# connectors.net
KiCad netlist of a schematic drawn in Altium Designer
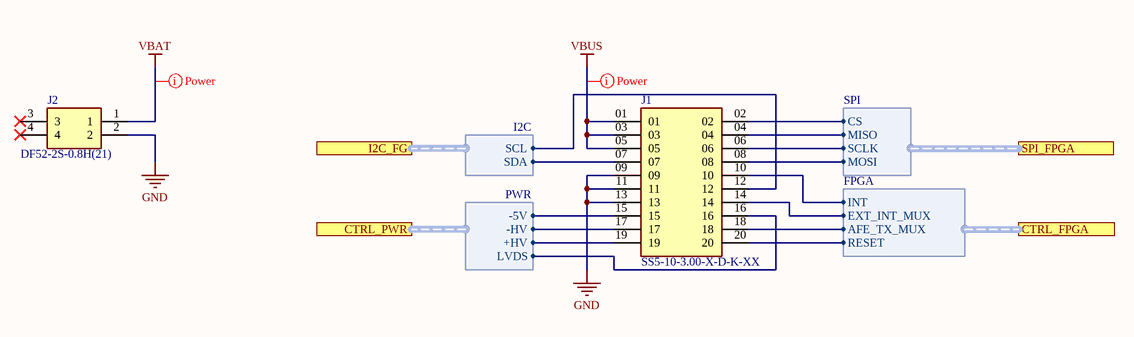
[diagram p0: connectors.SchDoc]

(export (version "E")
  (design (tool "Eeschema 10.0.6"))
  (components
    (comp (ref "J1")
      (value "SS5-10-3.00-X-D-K-XX")
      (footprint "wius:SAMTEC_SS5-10-3.00-X-D-K-XX")
      (description "0.50mm Socket Strip Assembly")
      (fields (field (name "MF") "Samtec Inc."))
      (libsource (lib "wius") (part "SS5-10-3.00-X-D-K-XX"))
    )
    (comp (ref "J2")
      (value "DF52-2S-0.8H(21)")
      (footprint "wius:DF522S08H21")
      (description "Connector")
      (fields (field (name "MOUSER PART NUMBER") "798-DF52-2S-0.8H21"))
      (libsource (lib "wius") (part "DF52-2S-0.8H_21_"))
    )
  )
  (nets
    (net (code "5") (name "/+HV") (class "Default")
      (node (ref "J1") (pin "19") (pinfunction "19_19") (pintype "passive"))
    )
    (net (code "6") (name "/-5V") (class "Default")
      (node (ref "J1") (pin "15") (pinfunction "15_15") (pintype "passive"))
    )
    (net (code "7") (name "/-HV") (class "Default")
      (node (ref "J1") (pin "17") (pinfunction "17_17") (pintype "passive"))
    )
    (net (code "8") (name "/AFE_TX_MUX") (class "Default")
      (node (ref "J1") (pin "18") (pinfunction "18_18") (pintype "passive"))
    )
    (net (code "9") (name "/CS") (class "Default")
      (node (ref "J1") (pin "02") (pinfunction "02_02") (pintype "passive"))
    )
    (net (code "10") (name "/EXT_INT_MUX") (class "Default")
      (node (ref "J1") (pin "14") (pinfunction "14_14") (pintype "passive"))
    )
    (net (code "11") (name "/INT") (class "Default")
      (node (ref "J1") (pin "10") (pinfunction "10_10") (pintype "passive"))
    )
    (net (code "12") (name "/LVDS") (class "Default")
      (node (ref "J1") (pin "16") (pinfunction "16_16") (pintype "passive"))
    )
    (net (code "13") (name "/MISO") (class "Default")
      (node (ref "J1") (pin "04") (pinfunction "04_04") (pintype "passive"))
    )
    (net (code "14") (name "/MOSI") (class "Default")
      (node (ref "J1") (pin "08") (pinfunction "08_08") (pintype "passive"))
    )
    (net (code "15") (name "/RESET") (class "Default")
      (node (ref "J1") (pin "20") (pinfunction "20_20") (pintype "passive"))
    )
    (net (code "16") (name "/SCL") (class "Default")
      (node (ref "J1") (pin "12") (pinfunction "12_12") (pintype "passive"))
    )
    (net (code "17") (name "/SCLK") (class "Default")
      (node (ref "J1") (pin "06") (pinfunction "06_06") (pintype "passive"))
    )
    (net (code "18") (name "/SDA") (class "Default")
      (node (ref "J1") (pin "07") (pinfunction "07_07") (pintype "passive"))
    )
    (net (code "23") (name "GND") (class "Default")
      (node (ref "J1") (pin "09") (pinfunction "09_09") (pintype "passive"))
      (node (ref "J1") (pin "11") (pinfunction "11_11") (pintype "passive"))
      (node (ref "J1") (pin "13") (pinfunction "13_13") (pintype "passive"))
      (node (ref "J2") (pin "2") (pinfunction "2_2") (pintype "passive"))
    )
    (net (code "24") (name "VBAT") (class "Default")
      (node (ref "J2") (pin "1") (pinfunction "1_1") (pintype "passive"))
    )
    (net (code "25") (name "VBUS") (class "Default")
      (node (ref "J1") (pin "01") (pinfunction "01_01") (pintype "passive"))
      (node (ref "J1") (pin "03") (pinfunction "03_03") (pintype "passive"))
      (node (ref "J1") (pin "05") (pinfunction "05_05") (pintype "passive"))
    )
    (net (code "26") (name "unconnected-(J2-Pad3)") (class "Default")
      (node (ref "J2") (pin "3") (pinfunction "3_3") (pintype "passive+no_connect"))
    )
    (net (code "27") (name "unconnected-(J2-Pad4)") (class "Default")
      (node (ref "J2") (pin "4") (pinfunction "4_4") (pintype "passive+no_connect"))
    )
  )
)
